# GEN1PINOUT.net
KiCad netlist of a schematic drawn in EAGLE
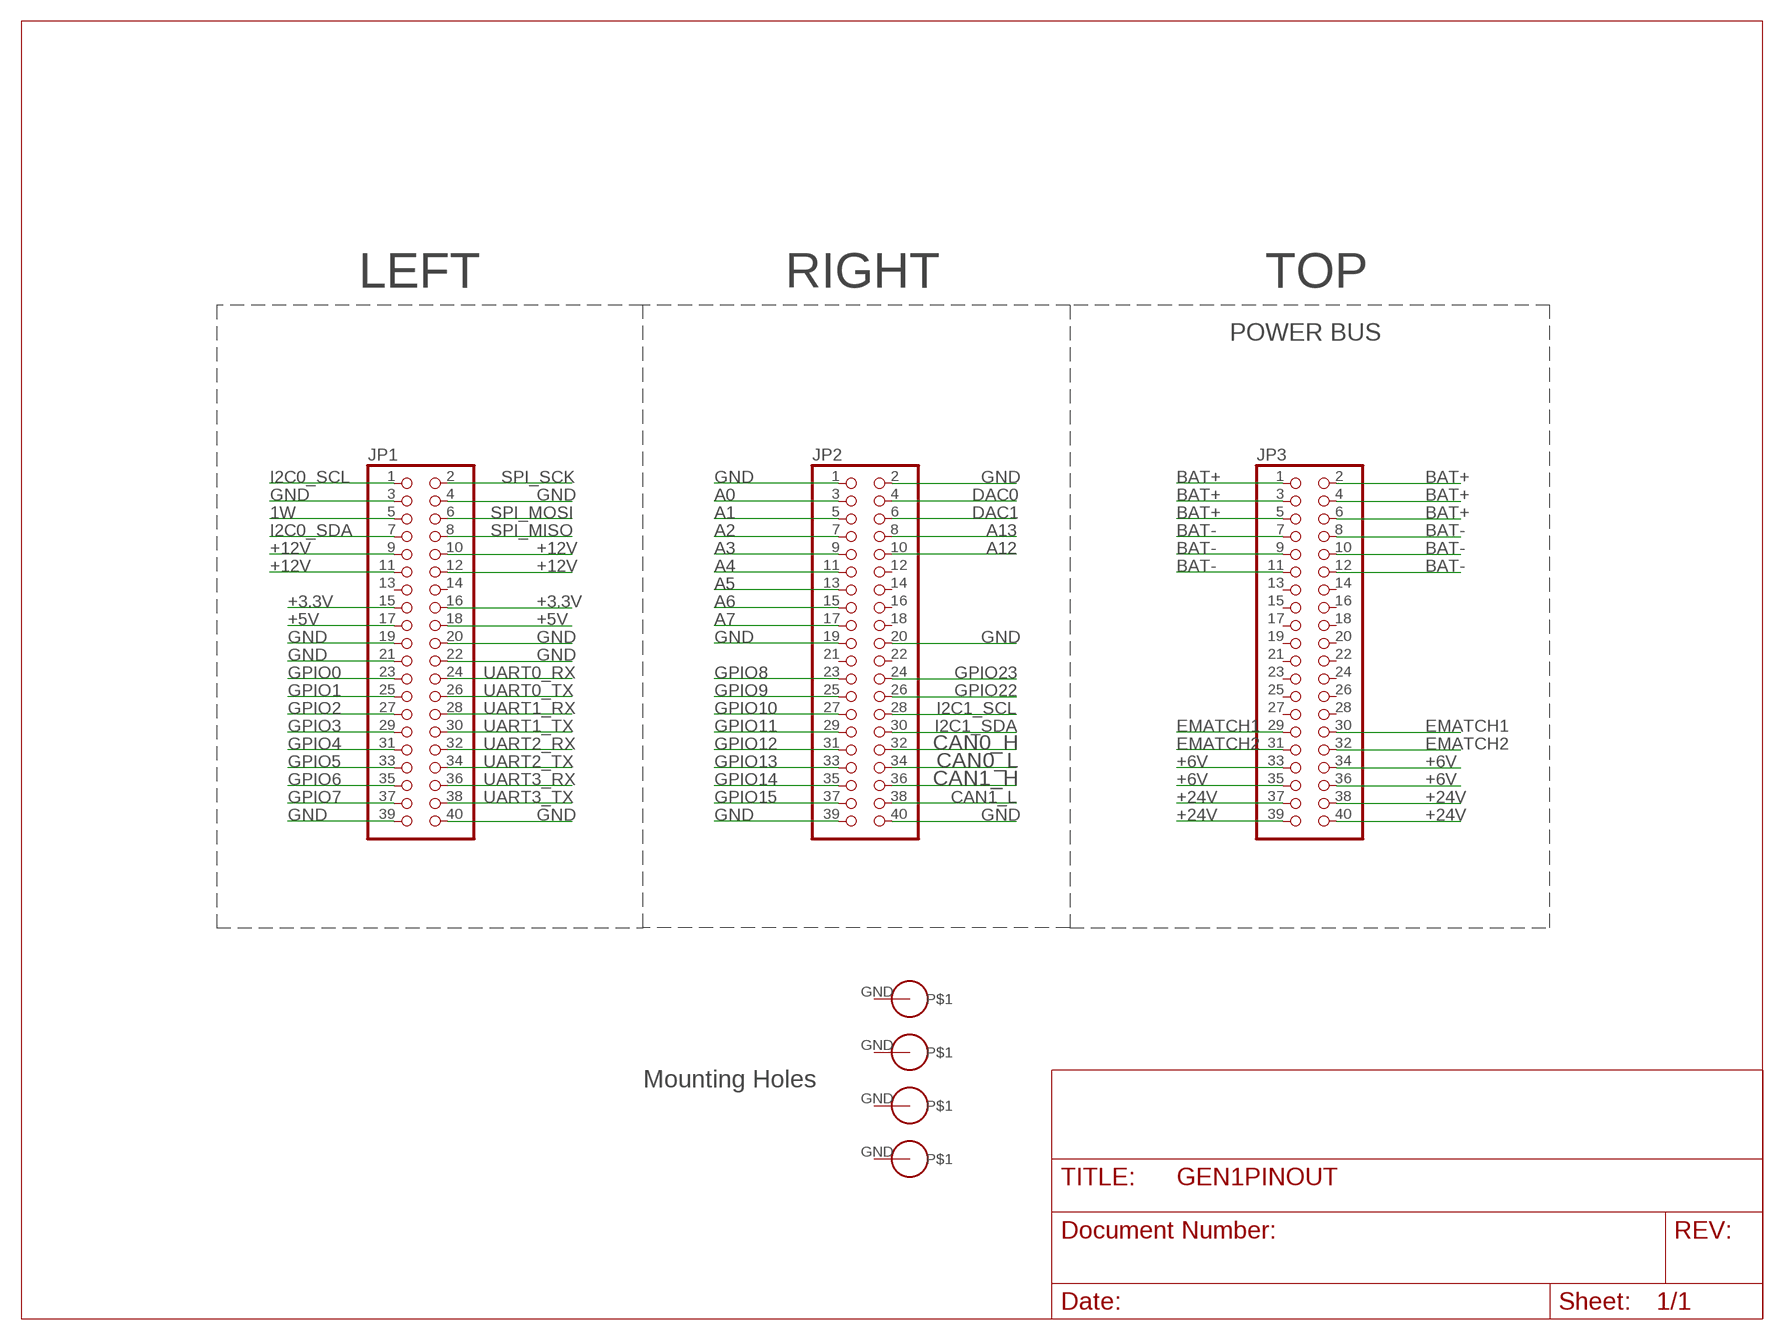
[diagram p0: schematic, sheet 1]

(export (version "E")
  (design (tool "Eeschema 10.0.6"))
  (components
    (comp (ref "$$U$1")
      (value "PS/104-MOUNTING-HOLE")
      (footprint "eagle-import:PC_104-MOUNTING-HOLE")
      (libsource (lib "eagle-import") (part "PS/104-MOUNTING-HOLE"))
    )
    (comp (ref "JP1")
      (value "PINHD-2X20")
      (footprint "eagle-import:2X20")
      (libsource (lib "eagle-import") (part "PINHD-2X20"))
    )
    (comp (ref "JP2")
      (value "PINHD-2X20")
      (footprint "eagle-import:2X20")
      (libsource (lib "eagle-import") (part "PINHD-2X20"))
    )
    (comp (ref "JP3")
      (value "PINHD-2X20")
      (footprint "eagle-import:2X20")
      (libsource (lib "eagle-import") (part "PINHD-2X20"))
    )
    (comp (ref "U$1")
      (value "PS/104-MOUNTING-HOLE")
      (footprint "eagle-import:PC_104-MOUNTING-HOLE")
      (libsource (lib "eagle-import") (part "PS/104-MOUNTING-HOLE"))
    )
    (comp (ref "U$2")
      (value "PS/104-MOUNTING-HOLE")
      (footprint "eagle-import:PC_104-MOUNTING-HOLE")
      (libsource (lib "eagle-import") (part "PS/104-MOUNTING-HOLE"))
    )
    (comp (ref "U$3")
      (value "PS/104-MOUNTING-HOLE")
      (footprint "eagle-import:PC_104-MOUNTING-HOLE")
      (libsource (lib "eagle-import") (part "PS/104-MOUNTING-HOLE"))
    )
  )
  (nets
    (net (code "1") (name "/+3.3V") (class "Default")
      (node (ref "JP1") (pin "15") (pinfunction "15_15") (pintype "passive"))
      (node (ref "JP1") (pin "16") (pinfunction "16_16") (pintype "passive"))
    )
    (net (code "2") (name "/+5V") (class "Default")
      (node (ref "JP1") (pin "17") (pinfunction "17_17") (pintype "passive"))
      (node (ref "JP1") (pin "18") (pinfunction "18_18") (pintype "passive"))
    )
    (net (code "3") (name "/+6V") (class "Default")
      (node (ref "JP3") (pin "33") (pinfunction "33_33") (pintype "passive"))
      (node (ref "JP3") (pin "34") (pinfunction "34_34") (pintype "passive"))
      (node (ref "JP3") (pin "35") (pinfunction "35_35") (pintype "passive"))
      (node (ref "JP3") (pin "36") (pinfunction "36_36") (pintype "passive"))
    )
    (net (code "4") (name "/+12V") (class "Default")
      (node (ref "JP1") (pin "10") (pinfunction "10_10") (pintype "passive"))
      (node (ref "JP1") (pin "11") (pinfunction "11_11") (pintype "passive"))
      (node (ref "JP1") (pin "12") (pinfunction "12_12") (pintype "passive"))
      (node (ref "JP1") (pin "9") (pinfunction "9_9") (pintype "passive"))
    )
    (net (code "5") (name "/+24V") (class "Default")
      (node (ref "JP3") (pin "37") (pinfunction "37_37") (pintype "passive"))
      (node (ref "JP3") (pin "38") (pinfunction "38_38") (pintype "passive"))
      (node (ref "JP3") (pin "39") (pinfunction "39_39") (pintype "passive"))
      (node (ref "JP3") (pin "40") (pinfunction "40_40") (pintype "passive"))
    )
    (net (code "6") (name "/1W") (class "Default")
      (node (ref "JP1") (pin "5") (pinfunction "5_5") (pintype "passive"))
    )
    (net (code "7") (name "/A0") (class "Default")
      (node (ref "JP2") (pin "3") (pinfunction "3_3") (pintype "passive"))
    )
    (net (code "8") (name "/A1") (class "Default")
      (node (ref "JP2") (pin "5") (pinfunction "5_5") (pintype "passive"))
    )
    (net (code "9") (name "/A2") (class "Default")
      (node (ref "JP2") (pin "7") (pinfunction "7_7") (pintype "passive"))
    )
    (net (code "10") (name "/A3") (class "Default")
      (node (ref "JP2") (pin "9") (pinfunction "9_9") (pintype "passive"))
    )
    (net (code "11") (name "/A4") (class "Default")
      (node (ref "JP2") (pin "11") (pinfunction "11_11") (pintype "passive"))
    )
    (net (code "12") (name "/A5") (class "Default")
      (node (ref "JP2") (pin "13") (pinfunction "13_13") (pintype "passive"))
    )
    (net (code "13") (name "/A6") (class "Default")
      (node (ref "JP2") (pin "15") (pinfunction "15_15") (pintype "passive"))
    )
    (net (code "14") (name "/A7") (class "Default")
      (node (ref "JP2") (pin "17") (pinfunction "17_17") (pintype "passive"))
    )
    (net (code "15") (name "/A12") (class "Default")
      (node (ref "JP2") (pin "10") (pinfunction "10_10") (pintype "passive"))
    )
    (net (code "16") (name "/A13") (class "Default")
      (node (ref "JP2") (pin "8") (pinfunction "8_8") (pintype "passive"))
    )
    (net (code "17") (name "/BAT+") (class "Default")
      (node (ref "JP3") (pin "1") (pinfunction "1_1") (pintype "passive"))
      (node (ref "JP3") (pin "2") (pinfunction "2_2") (pintype "passive"))
      (node (ref "JP3") (pin "3") (pinfunction "3_3") (pintype "passive"))
      (node (ref "JP3") (pin "4") (pinfunction "4_4") (pintype "passive"))
      (node (ref "JP3") (pin "5") (pinfunction "5_5") (pintype "passive"))
      (node (ref "JP3") (pin "6") (pinfunction "6_6") (pintype "passive"))
    )
    (net (code "18") (name "/BAT-") (class "Default")
      (node (ref "JP3") (pin "10") (pinfunction "10_10") (pintype "passive"))
      (node (ref "JP3") (pin "11") (pinfunction "11_11") (pintype "passive"))
      (node (ref "JP3") (pin "12") (pinfunction "12_12") (pintype "passive"))
      (node (ref "JP3") (pin "7") (pinfunction "7_7") (pintype "passive"))
      (node (ref "JP3") (pin "8") (pinfunction "8_8") (pintype "passive"))
      (node (ref "JP3") (pin "9") (pinfunction "9_9") (pintype "passive"))
    )
    (net (code "19") (name "/CAN0_H") (class "Default")
      (node (ref "JP2") (pin "32") (pinfunction "32_32") (pintype "passive"))
    )
    (net (code "20") (name "/CAN0_L") (class "Default")
      (node (ref "JP2") (pin "34") (pinfunction "34_34") (pintype "passive"))
    )
    (net (code "21") (name "/CAN1_H") (class "Default")
      (node (ref "JP2") (pin "36") (pinfunction "36_36") (pintype "passive"))
    )
    (net (code "22") (name "/CAN1_L") (class "Default")
      (node (ref "JP2") (pin "38") (pinfunction "38_38") (pintype "passive"))
    )
    (net (code "23") (name "/DAC0") (class "Default")
      (node (ref "JP2") (pin "4") (pinfunction "4_4") (pintype "passive"))
    )
    (net (code "24") (name "/DAC1") (class "Default")
      (node (ref "JP2") (pin "6") (pinfunction "6_6") (pintype "passive"))
    )
    (net (code "25") (name "/EMATCH1") (class "Default")
      (node (ref "JP3") (pin "29") (pinfunction "29_29") (pintype "passive"))
      (node (ref "JP3") (pin "30") (pinfunction "30_30") (pintype "passive"))
    )
    (net (code "26") (name "/EMATCH2") (class "Default")
      (node (ref "JP3") (pin "31") (pinfunction "31_31") (pintype "passive"))
      (node (ref "JP3") (pin "32") (pinfunction "32_32") (pintype "passive"))
    )
    (net (code "27") (name "/GND") (class "Default")
      (node (ref "JP1") (pin "19") (pinfunction "19_19") (pintype "passive"))
      (node (ref "JP1") (pin "20") (pinfunction "20_20") (pintype "passive"))
      (node (ref "JP1") (pin "21") (pinfunction "21_21") (pintype "passive"))
      (node (ref "JP1") (pin "22") (pinfunction "22_22") (pintype "passive"))
      (node (ref "JP1") (pin "3") (pinfunction "3_3") (pintype "passive"))
      (node (ref "JP1") (pin "39") (pinfunction "39_39") (pintype "passive"))
      (node (ref "JP1") (pin "4") (pinfunction "4_4") (pintype "passive"))
      (node (ref "JP1") (pin "40") (pinfunction "40_40") (pintype "passive"))
      (node (ref "JP2") (pin "1") (pinfunction "1_1") (pintype "passive"))
      (node (ref "JP2") (pin "19") (pinfunction "19_19") (pintype "passive"))
      (node (ref "JP2") (pin "2") (pinfunction "2_2") (pintype "passive"))
      (node (ref "JP2") (pin "20") (pinfunction "20_20") (pintype "passive"))
      (node (ref "JP2") (pin "39") (pinfunction "39_39") (pintype "passive"))
      (node (ref "JP2") (pin "40") (pinfunction "40_40") (pintype "passive"))
    )
    (net (code "28") (name "/GPIO0") (class "Default")
      (node (ref "JP1") (pin "23") (pinfunction "23_23") (pintype "passive"))
    )
    (net (code "29") (name "/GPIO1") (class "Default")
      (node (ref "JP1") (pin "25") (pinfunction "25_25") (pintype "passive"))
    )
    (net (code "30") (name "/GPIO2") (class "Default")
      (node (ref "JP1") (pin "27") (pinfunction "27_27") (pintype "passive"))
    )
    (net (code "31") (name "/GPIO3") (class "Default")
      (node (ref "JP1") (pin "29") (pinfunction "29_29") (pintype "passive"))
    )
    (net (code "32") (name "/GPIO4") (class "Default")
      (node (ref "JP1") (pin "31") (pinfunction "31_31") (pintype "passive"))
    )
    (net (code "33") (name "/GPIO5") (class "Default")
      (node (ref "JP1") (pin "33") (pinfunction "33_33") (pintype "passive"))
    )
    (net (code "34") (name "/GPIO6") (class "Default")
      (node (ref "JP1") (pin "35") (pinfunction "35_35") (pintype "passive"))
    )
    (net (code "35") (name "/GPIO7") (class "Default")
      (node (ref "JP1") (pin "37") (pinfunction "37_37") (pintype "passive"))
    )
    (net (code "36") (name "/GPIO8") (class "Default")
      (node (ref "JP2") (pin "23") (pinfunction "23_23") (pintype "passive"))
    )
    (net (code "37") (name "/GPIO9") (class "Default")
      (node (ref "JP2") (pin "25") (pinfunction "25_25") (pintype "passive"))
    )
    (net (code "38") (name "/GPIO10") (class "Default")
      (node (ref "JP2") (pin "27") (pinfunction "27_27") (pintype "passive"))
    )
    (net (code "39") (name "/GPIO11") (class "Default")
      (node (ref "JP2") (pin "29") (pinfunction "29_29") (pintype "passive"))
    )
    (net (code "40") (name "/GPIO12") (class "Default")
      (node (ref "JP2") (pin "31") (pinfunction "31_31") (pintype "passive"))
    )
    (net (code "41") (name "/GPIO13") (class "Default")
      (node (ref "JP2") (pin "33") (pinfunction "33_33") (pintype "passive"))
    )
    (net (code "42") (name "/GPIO14") (class "Default")
      (node (ref "JP2") (pin "35") (pinfunction "35_35") (pintype "passive"))
    )
    (net (code "43") (name "/GPIO15") (class "Default")
      (node (ref "JP2") (pin "37") (pinfunction "37_37") (pintype "passive"))
    )
    (net (code "44") (name "/GPIO22") (class "Default")
      (node (ref "JP2") (pin "26") (pinfunction "26_26") (pintype "passive"))
    )
    (net (code "45") (name "/GPIO23") (class "Default")
      (node (ref "JP2") (pin "24") (pinfunction "24_24") (pintype "passive"))
    )
    (net (code "46") (name "/I2C0_SCL") (class "Default")
      (node (ref "JP1") (pin "1") (pinfunction "1_1") (pintype "passive"))
    )
    (net (code "47") (name "/I2C0_SDA") (class "Default")
      (node (ref "JP1") (pin "7") (pinfunction "7_7") (pintype "passive"))
    )
    (net (code "48") (name "/I2C1_SCL") (class "Default")
      (node (ref "JP2") (pin "28") (pinfunction "28_28") (pintype "passive"))
    )
    (net (code "49") (name "/I2C1_SDA") (class "Default")
      (node (ref "JP2") (pin "30") (pinfunction "30_30") (pintype "passive"))
    )
    (net (code "50") (name "/SPI_MISO") (class "Default")
      (node (ref "JP1") (pin "8") (pinfunction "8_8") (pintype "passive"))
    )
    (net (code "51") (name "/SPI_MOSI") (class "Default")
      (node (ref "JP1") (pin "6") (pinfunction "6_6") (pintype "passive"))
    )
    (net (code "52") (name "/SPI_SCK") (class "Default")
      (node (ref "JP1") (pin "2") (pinfunction "2_2") (pintype "passive"))
    )
    (net (code "53") (name "/UART0_RX") (class "Default")
      (node (ref "JP1") (pin "24") (pinfunction "24_24") (pintype "passive"))
    )
    (net (code "54") (name "/UART0_TX") (class "Default")
      (node (ref "JP1") (pin "26") (pinfunction "26_26") (pintype "passive"))
    )
    (net (code "55") (name "/UART1_RX") (class "Default")
      (node (ref "JP1") (pin "28") (pinfunction "28_28") (pintype "passive"))
    )
    (net (code "56") (name "/UART1_TX") (class "Default")
      (node (ref "JP1") (pin "30") (pinfunction "30_30") (pintype "passive"))
    )
    (net (code "57") (name "/UART2_RX") (class "Default")
      (node (ref "JP1") (pin "32") (pinfunction "32_32") (pintype "passive"))
    )
    (net (code "58") (name "/UART2_TX") (class "Default")
      (node (ref "JP1") (pin "34") (pinfunction "34_34") (pintype "passive"))
    )
    (net (code "59") (name "/UART3_RX") (class "Default")
      (node (ref "JP1") (pin "36") (pinfunction "36_36") (pintype "passive"))
    )
    (net (code "60") (name "/UART3_TX") (class "Default")
      (node (ref "JP1") (pin "38") (pinfunction "38_38") (pintype "passive"))
    )
    (net (code "61") (name "unconnected-($$U$1-P$1-PadGND)") (class "Default")
      (node (ref "$$U$1") (pin "GND") (pinfunction "P$1_GND") (pintype "bidirectional"))
    )
    (net (code "62") (name "unconnected-(JP1-Pad13)") (class "Default")
      (node (ref "JP1") (pin "13") (pinfunction "13_13") (pintype "passive"))
    )
    (net (code "63") (name "unconnected-(JP1-Pad14)") (class "Default")
      (node (ref "JP1") (pin "14") (pinfunction "14_14") (pintype "passive"))
    )
    (net (code "64") (name "unconnected-(JP2-Pad12)") (class "Default")
      (node (ref "JP2") (pin "12") (pinfunction "12_12") (pintype "passive"))
    )
    (net (code "65") (name "unconnected-(JP2-Pad14)") (class "Default")
      (node (ref "JP2") (pin "14") (pinfunction "14_14") (pintype "passive"))
    )
    (net (code "66") (name "unconnected-(JP2-Pad16)") (class "Default")
      (node (ref "JP2") (pin "16") (pinfunction "16_16") (pintype "passive"))
    )
    (net (code "67") (name "unconnected-(JP2-Pad18)") (class "Default")
      (node (ref "JP2") (pin "18") (pinfunction "18_18") (pintype "passive"))
    )
    (net (code "68") (name "unconnected-(JP2-Pad21)") (class "Default")
      (node (ref "JP2") (pin "21") (pinfunction "21_21") (pintype "passive"))
    )
    (net (code "69") (name "unconnected-(JP2-Pad22)") (class "Default")
      (node (ref "JP2") (pin "22") (pinfunction "22_22") (pintype "passive"))
    )
    (net (code "70") (name "unconnected-(JP3-Pad13)") (class "Default")
      (node (ref "JP3") (pin "13") (pinfunction "13_13") (pintype "passive"))
    )
    (net (code "71") (name "unconnected-(JP3-Pad14)") (class "Default")
      (node (ref "JP3") (pin "14") (pinfunction "14_14") (pintype "passive"))
    )
    (net (code "72") (name "unconnected-(JP3-Pad15)") (class "Default")
      (node (ref "JP3") (pin "15") (pinfunction "15_15") (pintype "passive"))
    )
    (net (code "73") (name "unconnected-(JP3-Pad16)") (class "Default")
      (node (ref "JP3") (pin "16") (pinfunction "16_16") (pintype "passive"))
    )
    (net (code "74") (name "unconnected-(JP3-Pad17)") (class "Default")
      (node (ref "JP3") (pin "17") (pinfunction "17_17") (pintype "passive"))
    )
    (net (code "75") (name "unconnected-(JP3-Pad18)") (class "Default")
      (node (ref "JP3") (pin "18") (pinfunction "18_18") (pintype "passive"))
    )
    (net (code "76") (name "unconnected-(JP3-Pad19)") (class "Default")
      (node (ref "JP3") (pin "19") (pinfunction "19_19") (pintype "passive"))
    )
    (net (code "77") (name "unconnected-(JP3-Pad20)") (class "Default")
      (node (ref "JP3") (pin "20") (pinfunction "20_20") (pintype "passive"))
    )
    (net (code "78") (name "unconnected-(JP3-Pad21)") (class "Default")
      (node (ref "JP3") (pin "21") (pinfunction "21_21") (pintype "passive"))
    )
    (net (code "79") (name "unconnected-(JP3-Pad22)") (class "Default")
      (node (ref "JP3") (pin "22") (pinfunction "22_22") (pintype "passive"))
    )
    (net (code "80") (name "unconnected-(JP3-Pad23)") (class "Default")
      (node (ref "JP3") (pin "23") (pinfunction "23_23") (pintype "passive"))
    )
    (net (code "81") (name "unconnected-(JP3-Pad24)") (class "Default")
      (node (ref "JP3") (pin "24") (pinfunction "24_24") (pintype "passive"))
    )
    (net (code "82") (name "unconnected-(JP3-Pad25)") (class "Default")
      (node (ref "JP3") (pin "25") (pinfunction "25_25") (pintype "passive"))
    )
    (net (code "83") (name "unconnected-(JP3-Pad26)") (class "Default")
      (node (ref "JP3") (pin "26") (pinfunction "26_26") (pintype "passive"))
    )
    (net (code "84") (name "unconnected-(JP3-Pad27)") (class "Default")
      (node (ref "JP3") (pin "27") (pinfunction "27_27") (pintype "passive"))
    )
    (net (code "85") (name "unconnected-(JP3-Pad28)") (class "Default")
      (node (ref "JP3") (pin "28") (pinfunction "28_28") (pintype "passive"))
    )
    (net (code "86") (name "unconnected-(U$1-P$1-PadGND)") (class "Default")
      (node (ref "U$1") (pin "GND") (pinfunction "P$1_GND") (pintype "bidirectional"))
    )
    (net (code "87") (name "unconnected-(U$2-P$1-PadGND)") (class "Default")
      (node (ref "U$2") (pin "GND") (pinfunction "P$1_GND") (pintype "bidirectional"))
    )
    (net (code "88") (name "unconnected-(U$3-P$1-PadGND)") (class "Default")
      (node (ref "U$3") (pin "GND") (pinfunction "P$1_GND") (pintype "bidirectional"))
    )
  )
)
